# flexTouch_v2.net
KiCad netlist of a schematic drawn in EasyEDA Pro
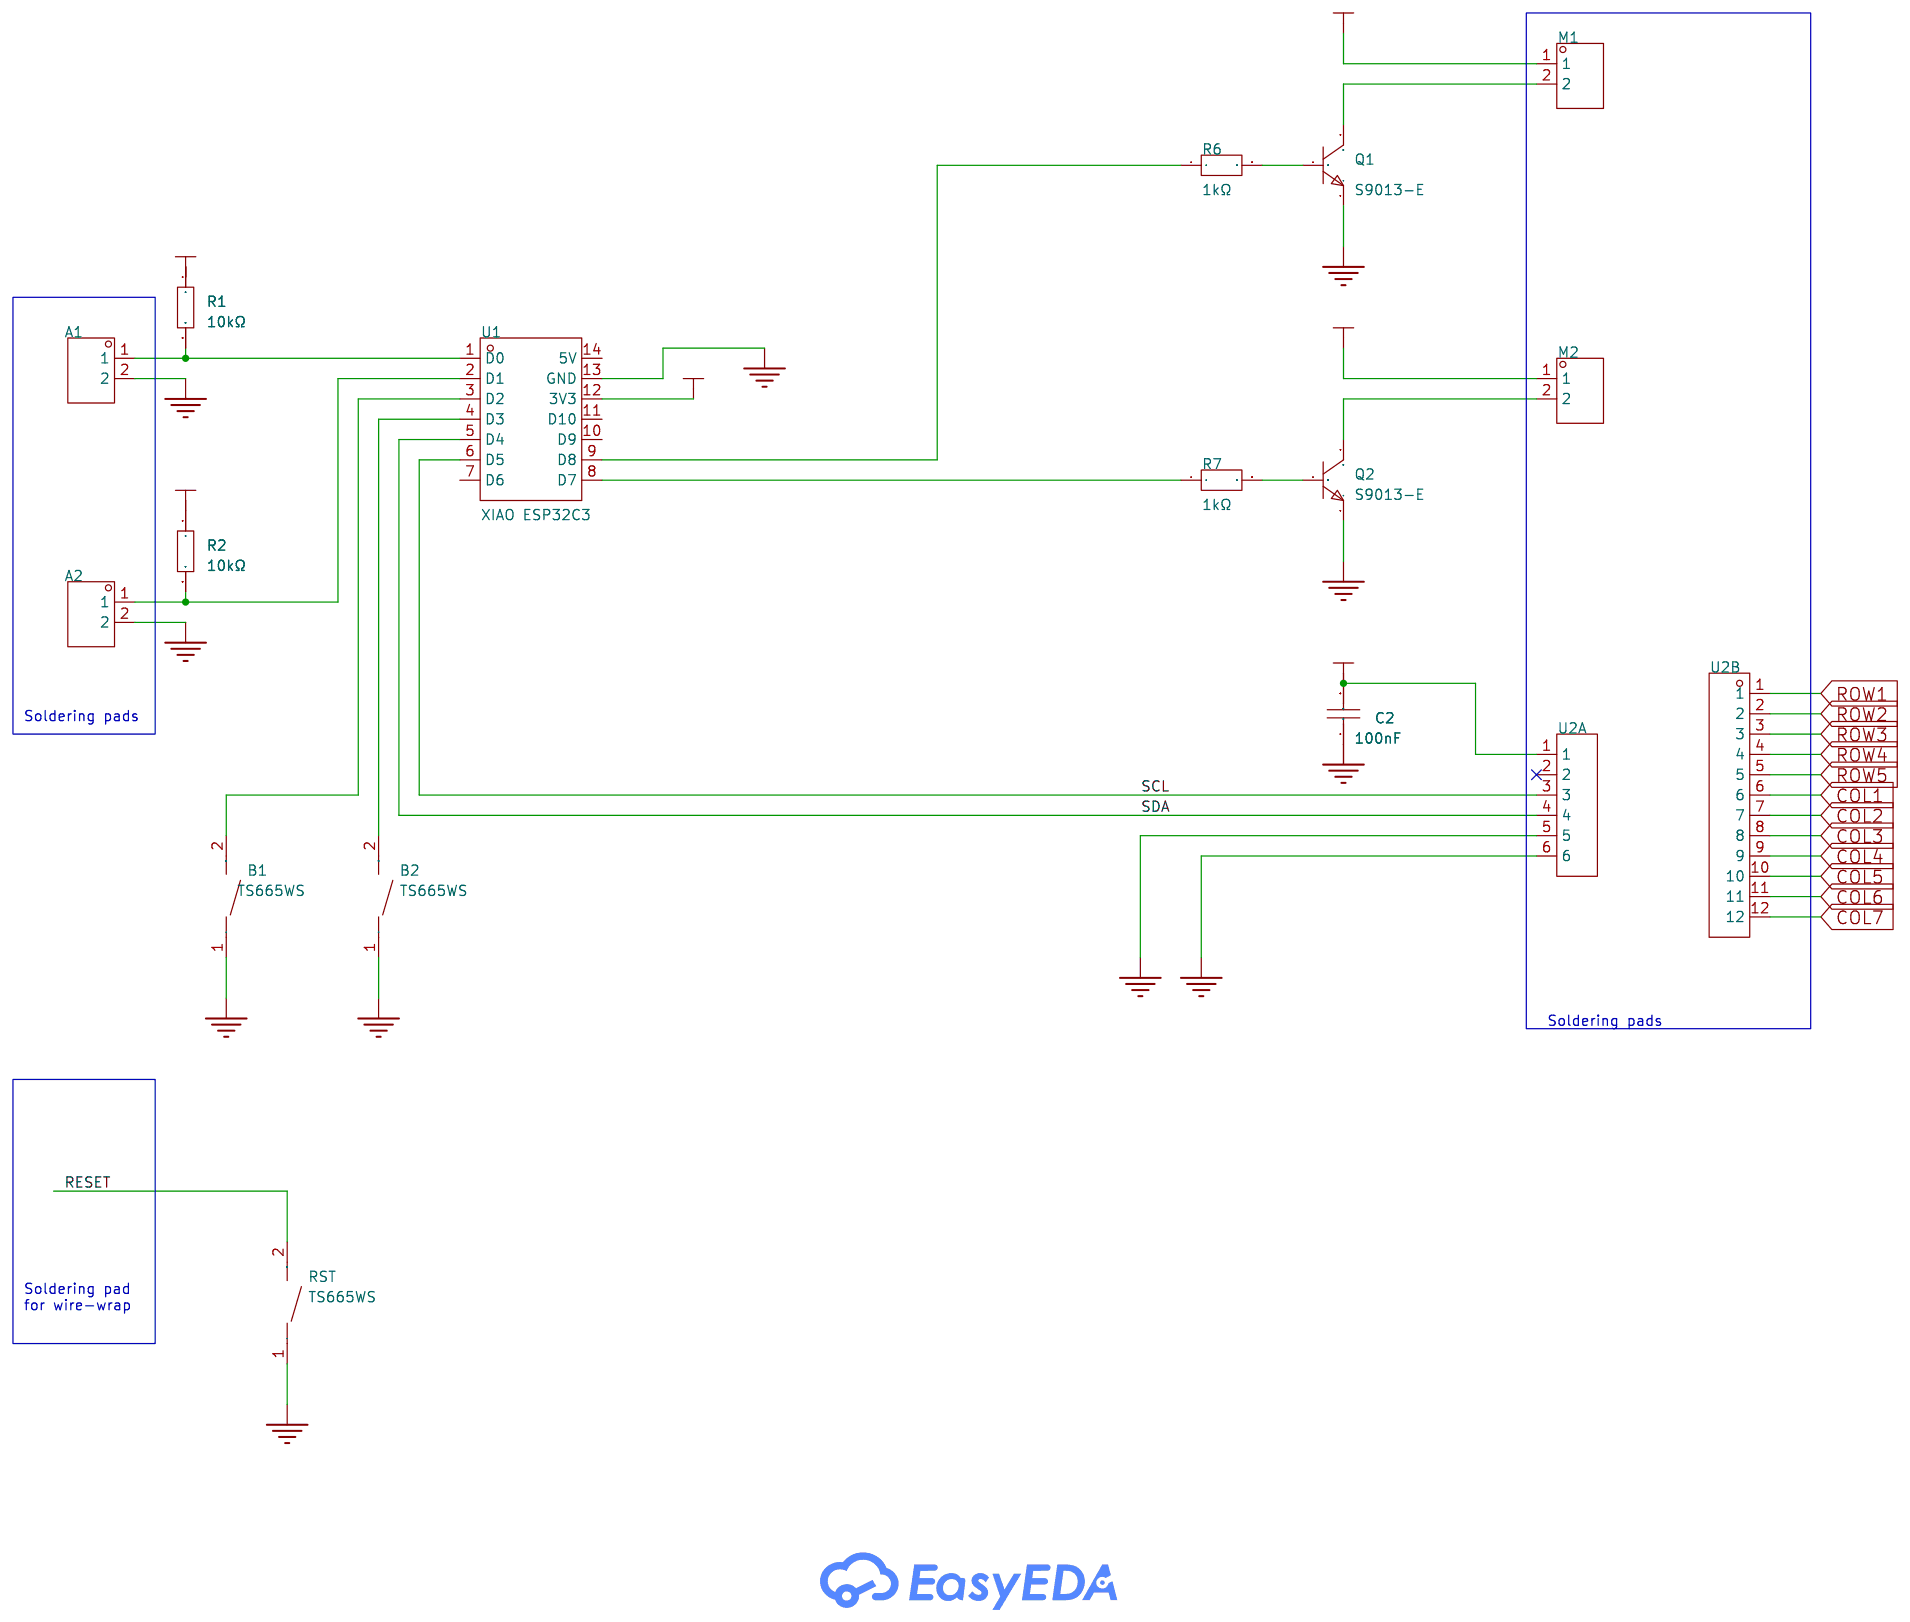
[diagram p0: schematic sheet]

(export (version "E")
  (design (tool "Eeschema 10.0.6"))
  (components
    (comp (ref "A1")
      (value "B-2200S02P-A120")
      (footprint "easyedapro:HDR-TH_2P-P2.54-V-F")
      (description "插孔结构:1x2P;间距:2.54mm;行距:-;安装类型:直插;排数:单排;总孔位数:2P;塑高:-;触头材质:黄铜;触头镀层:-;")
      (fields (field (name "Manufacturer") "Ckmtw(灿科盟)"))
      (libsource (lib "easyedapro") (part "220S-1*2P H=8.5MM Ytype Gold-plated"))
    )
    (comp (ref "A2")
      (value "B-2200S02P-A120")
      (footprint "easyedapro:HDR-TH_2P-P2.54-V-F")
      (description "插孔结构:1x2P;间距:2.54mm;行距:-;安装类型:直插;排数:单排;总孔位数:2P;塑高:-;触头材质:黄铜;触头镀层:-;")
      (fields (field (name "Manufacturer") "Ckmtw(灿科盟)"))
      (libsource (lib "easyedapro") (part "220S-1*2P H=8.5MM Ytype Gold-plated"))
    )
    (comp (ref "B1")
      (value "TS665WS")
      (footprint "easyedapro:SW-SMD_L6.0-W6.0-LS6.6")
      (fields (field (name "Manufacturer") "SHOU HAN(首韩)"))
      (libsource (lib "easyedapro") (part "TS665WS"))
    )
    (comp (ref "B2")
      (value "TS665WS")
      (footprint "easyedapro:SW-SMD_L6.0-W6.0-LS6.6")
      (fields (field (name "Manufacturer") "SHOU HAN(首韩)"))
      (libsource (lib "easyedapro") (part "TS665WS"))
    )
    (comp (ref "C2")
      (value "100nF")
      (footprint "easyedapro:C0603")
      (description "Capacitance:100nF Tolerance:±10% Tolerance:±10% Voltage Rating:50V Temperature Coefficient:X7R")
      (fields (field (name "Manufacturer Part") "0603B104K500NT") (field (name "Manufacturer") "FH(风华)"))
      (libsource (lib "easyedapro") (part "0603B104K500NT"))
    )
    (comp (ref "M1")
      (value "B-2200S02P-A120")
      (footprint "easyedapro:HDR-TH_2P-P2.54-V-F")
      (description "插孔结构:1x2P;间距:2.54mm;行距:-;安装类型:直插;排数:单排;总孔位数:2P;塑高:-;触头材质:黄铜;触头镀层:-;")
      (fields (field (name "Manufacturer") "Ckmtw(灿科盟)"))
      (libsource (lib "easyedapro") (part "220S-1*2P H=8.5MM Ytype Gold-plated"))
    )
    (comp (ref "M2")
      (value "B-2200S02P-A120")
      (footprint "easyedapro:HDR-TH_2P-P2.54-V-F")
      (description "插孔结构:1x2P;间距:2.54mm;行距:-;安装类型:直插;排数:单排;总孔位数:2P;塑高:-;触头材质:黄铜;触头镀层:-;")
      (fields (field (name "Manufacturer") "Ckmtw(灿科盟)"))
      (libsource (lib "easyedapro") (part "220S-1*2P H=8.5MM Ytype Gold-plated"))
    )
    (comp (ref "Q1")
      (value "S9013-E")
      (footprint "easyedapro:SOT-23-3_L2.9-W1.3-P1.90-LS2.4-BR")
      (description "晶体管类型:NPN;集电极电流(Ic):500mA;集射极击穿电压(Vceo):25V;耗散功率(Pd):300mW;直流电流增益(hFE):120@50mA,1V;")
      (fields (field (name "Manufacturer") "MDD(辰达半导体)"))
      (libsource (lib "easyedapro") (part "S9013-E"))
    )
    (comp (ref "Q2")
      (value "S9013-E")
      (footprint "easyedapro:SOT-23-3_L2.9-W1.3-P1.90-LS2.4-BR")
      (description "晶体管类型:NPN;集电极电流(Ic):500mA;集射极击穿电压(Vceo):25V;耗散功率(Pd):300mW;直流电流增益(hFE):120@50mA,1V;")
      (fields (field (name "Manufacturer") "MDD(辰达半导体)"))
      (libsource (lib "easyedapro") (part "S9013-E"))
    )
    (comp (ref "R1")
      (value "10kΩ")
      (footprint "easyedapro:R0603")
      (fields (field (name "Manufacturer Part") "RC0603FR-0710KL") (field (name "Manufacturer") "YAGEO(国巨)"))
      (libsource (lib "easyedapro") (part "RC0603FR-0710KL"))
    )
    (comp (ref "R2")
      (value "10kΩ")
      (footprint "easyedapro:R0603")
      (fields (field (name "Manufacturer Part") "RC0603FR-0710KL") (field (name "Manufacturer") "YAGEO(国巨)"))
      (libsource (lib "easyedapro") (part "RC0603FR-0710KL"))
    )
    (comp (ref "R6")
      (value "1kΩ")
      (footprint "easyedapro:R0603")
      (description "电阻类型:厚膜电阻;阻值:1kΩ;精度:±5%;功率:100mW;最大工作电压:75V;")
      (fields (field (name "Manufacturer Part") "SCR0603J1K") (field (name "Manufacturer") "VO(翔胜)"))
      (libsource (lib "easyedapro") (part "SCR0603J1K"))
    )
    (comp (ref "R7")
      (value "1kΩ")
      (footprint "easyedapro:R0603")
      (description "电阻类型:厚膜电阻;阻值:1kΩ;精度:±5%;功率:100mW;最大工作电压:75V;")
      (fields (field (name "Manufacturer Part") "SCR0603J1K") (field (name "Manufacturer") "VO(翔胜)"))
      (libsource (lib "easyedapro") (part "SCR0603J1K"))
    )
    (comp (ref "RST")
      (value "TS665WS")
      (footprint "easyedapro:SW-SMD_L6.0-W6.0-LS6.6")
      (fields (field (name "Manufacturer") "SHOU HAN(首韩)"))
      (libsource (lib "easyedapro") (part "TS665WS"))
    )
    (comp (ref "U1")
      (value "XIAO ESP32C3")
      (footprint "easyedapro:COMM-SMD_KQ-2801_V106")
      (libsource (lib "easyedapro") (part "XIAO ESP32C3"))
    )
    (comp (ref "U2A")
      (value "2.54-1*6")
      (footprint "easyedapro:HDR-TH_6P-P2.54-V-M")
      (description "Pin Structure:1x6P Pitch:2.54mm Number of Rows:Single Row Number of Pins:6P")
      (fields (field (name "Manufacturer") "ZHOURI(洲日)"))
      (libsource (lib "easyedapro") (part "2.54-1*6"))
    )
    (comp (ref "U2B")
      (value "PM2.54-1*12")
      (footprint "easyedapro:HDR-TH_12P-P2.54-V-F")
      (fields (field (name "Manufacturer") "ZHOURI(洲日)"))
      (libsource (lib "easyedapro") (part "PM2.54-1*12"))
    )
  )
  (nets
    (net (code "1") (name "/RESET") (class "Default")
      (node (ref "RST") (pin "2") (pinfunction "B_2") (pintype "unspecified"))
    )
    (net (code "2") (name "/SCL") (class "Default")
      (node (ref "U1") (pin "6") (pinfunction "D5_6") (pintype "unspecified"))
      (node (ref "U2A") (pin "3") (pinfunction "3_3") (pintype "unspecified"))
    )
    (net (code "3") (name "/SDA") (class "Default")
      (node (ref "U1") (pin "5") (pinfunction "D4_5") (pintype "unspecified"))
      (node (ref "U2A") (pin "4") (pinfunction "4_4") (pintype "unspecified"))
    )
    (net (code "4") (name "3V3") (class "Default")
      (node (ref "C2") (pin "2") (pinfunction "2_2") (pintype "input"))
      (node (ref "M1") (pin "1") (pinfunction "1_1") (pintype "unspecified"))
      (node (ref "M2") (pin "1") (pinfunction "1_1") (pintype "unspecified"))
      (node (ref "R1") (pin "1") (pinfunction "1_1") (pintype "input"))
      (node (ref "R2") (pin "1") (pinfunction "1_1") (pintype "input"))
      (node (ref "U1") (pin "12") (pinfunction "3V3_12") (pintype "unspecified"))
      (node (ref "U2A") (pin "1") (pinfunction "1_1") (pintype "unspecified"))
    )
    (net (code "5") (name "COL1") (class "Default")
      (node (ref "U2B") (pin "6") (pinfunction "6_6") (pintype "unspecified"))
    )
    (net (code "6") (name "COL2") (class "Default")
      (node (ref "U2B") (pin "7") (pinfunction "7_7") (pintype "unspecified"))
    )
    (net (code "7") (name "COL3") (class "Default")
      (node (ref "U2B") (pin "8") (pinfunction "8_8") (pintype "unspecified"))
    )
    (net (code "8") (name "COL4") (class "Default")
      (node (ref "U2B") (pin "9") (pinfunction "9_9") (pintype "unspecified"))
    )
    (net (code "9") (name "COL5") (class "Default")
      (node (ref "U2B") (pin "10") (pinfunction "10_10") (pintype "unspecified"))
    )
    (net (code "10") (name "COL6") (class "Default")
      (node (ref "U2B") (pin "11") (pinfunction "11_11") (pintype "unspecified"))
    )
    (net (code "11") (name "COL7") (class "Default")
      (node (ref "U2B") (pin "12") (pinfunction "12_12") (pintype "unspecified"))
    )
    (net (code "12") (name "GND") (class "Default")
      (node (ref "A1") (pin "2") (pinfunction "2_2") (pintype "unspecified"))
      (node (ref "A2") (pin "2") (pinfunction "2_2") (pintype "unspecified"))
      (node (ref "B1") (pin "1") (pinfunction "A_1") (pintype "unspecified"))
      (node (ref "B2") (pin "1") (pinfunction "A_1") (pintype "unspecified"))
      (node (ref "C2") (pin "1") (pinfunction "1_1") (pintype "input"))
      (node (ref "Q1") (pin "2") (pinfunction "E_2") (pintype "input"))
      (node (ref "Q2") (pin "2") (pinfunction "E_2") (pintype "input"))
      (node (ref "RST") (pin "1") (pinfunction "A_1") (pintype "unspecified"))
      (node (ref "U1") (pin "13") (pinfunction "GND_13") (pintype "unspecified"))
      (node (ref "U2A") (pin "5") (pinfunction "5_5") (pintype "unspecified"))
      (node (ref "U2A") (pin "6") (pinfunction "6_6") (pintype "unspecified"))
    )
    (net (code "13") (name "Net-(B1-B)") (class "Default")
      (node (ref "B1") (pin "2") (pinfunction "B_2") (pintype "unspecified"))
      (node (ref "U1") (pin "3") (pinfunction "D2_3") (pintype "unspecified"))
    )
    (net (code "14") (name "Net-(B2-B)") (class "Default")
      (node (ref "B2") (pin "2") (pinfunction "B_2") (pintype "unspecified"))
      (node (ref "U1") (pin "4") (pinfunction "D3_4") (pintype "unspecified"))
    )
    (net (code "15") (name "Net-(Q1-B)") (class "Default")
      (node (ref "Q1") (pin "1") (pinfunction "B_1") (pintype "input"))
      (node (ref "R6") (pin "2") (pinfunction "2_2") (pintype "unspecified"))
    )
    (net (code "16") (name "Net-(Q1-C)") (class "Default")
      (node (ref "M1") (pin "2") (pinfunction "2_2") (pintype "unspecified"))
      (node (ref "Q1") (pin "3") (pinfunction "C_3") (pintype "input"))
    )
    (net (code "17") (name "Net-(Q2-B)") (class "Default")
      (node (ref "Q2") (pin "1") (pinfunction "B_1") (pintype "input"))
      (node (ref "R7") (pin "2") (pinfunction "2_2") (pintype "unspecified"))
    )
    (net (code "18") (name "Net-(Q2-C)") (class "Default")
      (node (ref "M2") (pin "2") (pinfunction "2_2") (pintype "unspecified"))
      (node (ref "Q2") (pin "3") (pinfunction "C_3") (pintype "input"))
    )
    (net (code "19") (name "Net-(U1-D0)") (class "Default")
      (node (ref "A1") (pin "1") (pinfunction "1_1") (pintype "unspecified"))
      (node (ref "R1") (pin "2") (pinfunction "2_2") (pintype "input"))
      (node (ref "U1") (pin "1") (pinfunction "D0_1") (pintype "unspecified"))
    )
    (net (code "20") (name "Net-(U1-D1)") (class "Default")
      (node (ref "A2") (pin "1") (pinfunction "1_1") (pintype "unspecified"))
      (node (ref "R2") (pin "2") (pinfunction "2_2") (pintype "input"))
      (node (ref "U1") (pin "2") (pinfunction "D1_2") (pintype "unspecified"))
    )
    (net (code "21") (name "Net-(U1-D7)") (class "Default")
      (node (ref "R7") (pin "1") (pinfunction "1_1") (pintype "unspecified"))
      (node (ref "U1") (pin "8") (pinfunction "D7_8") (pintype "unspecified"))
    )
    (net (code "22") (name "Net-(U1-D8)") (class "Default")
      (node (ref "R6") (pin "1") (pinfunction "1_1") (pintype "unspecified"))
      (node (ref "U1") (pin "9") (pinfunction "D8_9") (pintype "unspecified"))
    )
    (net (code "23") (name "ROW1") (class "Default")
      (node (ref "U2B") (pin "1") (pinfunction "1_1") (pintype "unspecified"))
    )
    (net (code "24") (name "ROW2") (class "Default")
      (node (ref "U2B") (pin "2") (pinfunction "2_2") (pintype "unspecified"))
    )
    (net (code "25") (name "ROW3") (class "Default")
      (node (ref "U2B") (pin "3") (pinfunction "3_3") (pintype "unspecified"))
    )
    (net (code "26") (name "ROW4") (class "Default")
      (node (ref "U2B") (pin "4") (pinfunction "4_4") (pintype "unspecified"))
    )
    (net (code "27") (name "ROW5") (class "Default")
      (node (ref "U2B") (pin "5") (pinfunction "5_5") (pintype "unspecified"))
    )
    (net (code "28") (name "unconnected-(U1-5V-Pad14)") (class "Default")
      (node (ref "U1") (pin "14") (pinfunction "5V_14") (pintype "unspecified"))
    )
    (net (code "29") (name "unconnected-(U1-D6-Pad7)") (class "Default")
      (node (ref "U1") (pin "7") (pinfunction "D6_7") (pintype "unspecified"))
    )
    (net (code "30") (name "unconnected-(U1-D9-Pad10)") (class "Default")
      (node (ref "U1") (pin "10") (pinfunction "D9_10") (pintype "unspecified"))
    )
    (net (code "31") (name "unconnected-(U1-D10-Pad11)") (class "Default")
      (node (ref "U1") (pin "11") (pinfunction "D10_11") (pintype "unspecified"))
    )
    (net (code "32") (name "unconnected-(U2A-Pad2)") (class "Default")
      (node (ref "U2A") (pin "2") (pinfunction "2_2") (pintype "unspecified+no_connect"))
    )
  )
)
